# IP2363_DEMO_V1_10.net
KiCad netlist of a schematic drawn in Altium Designer
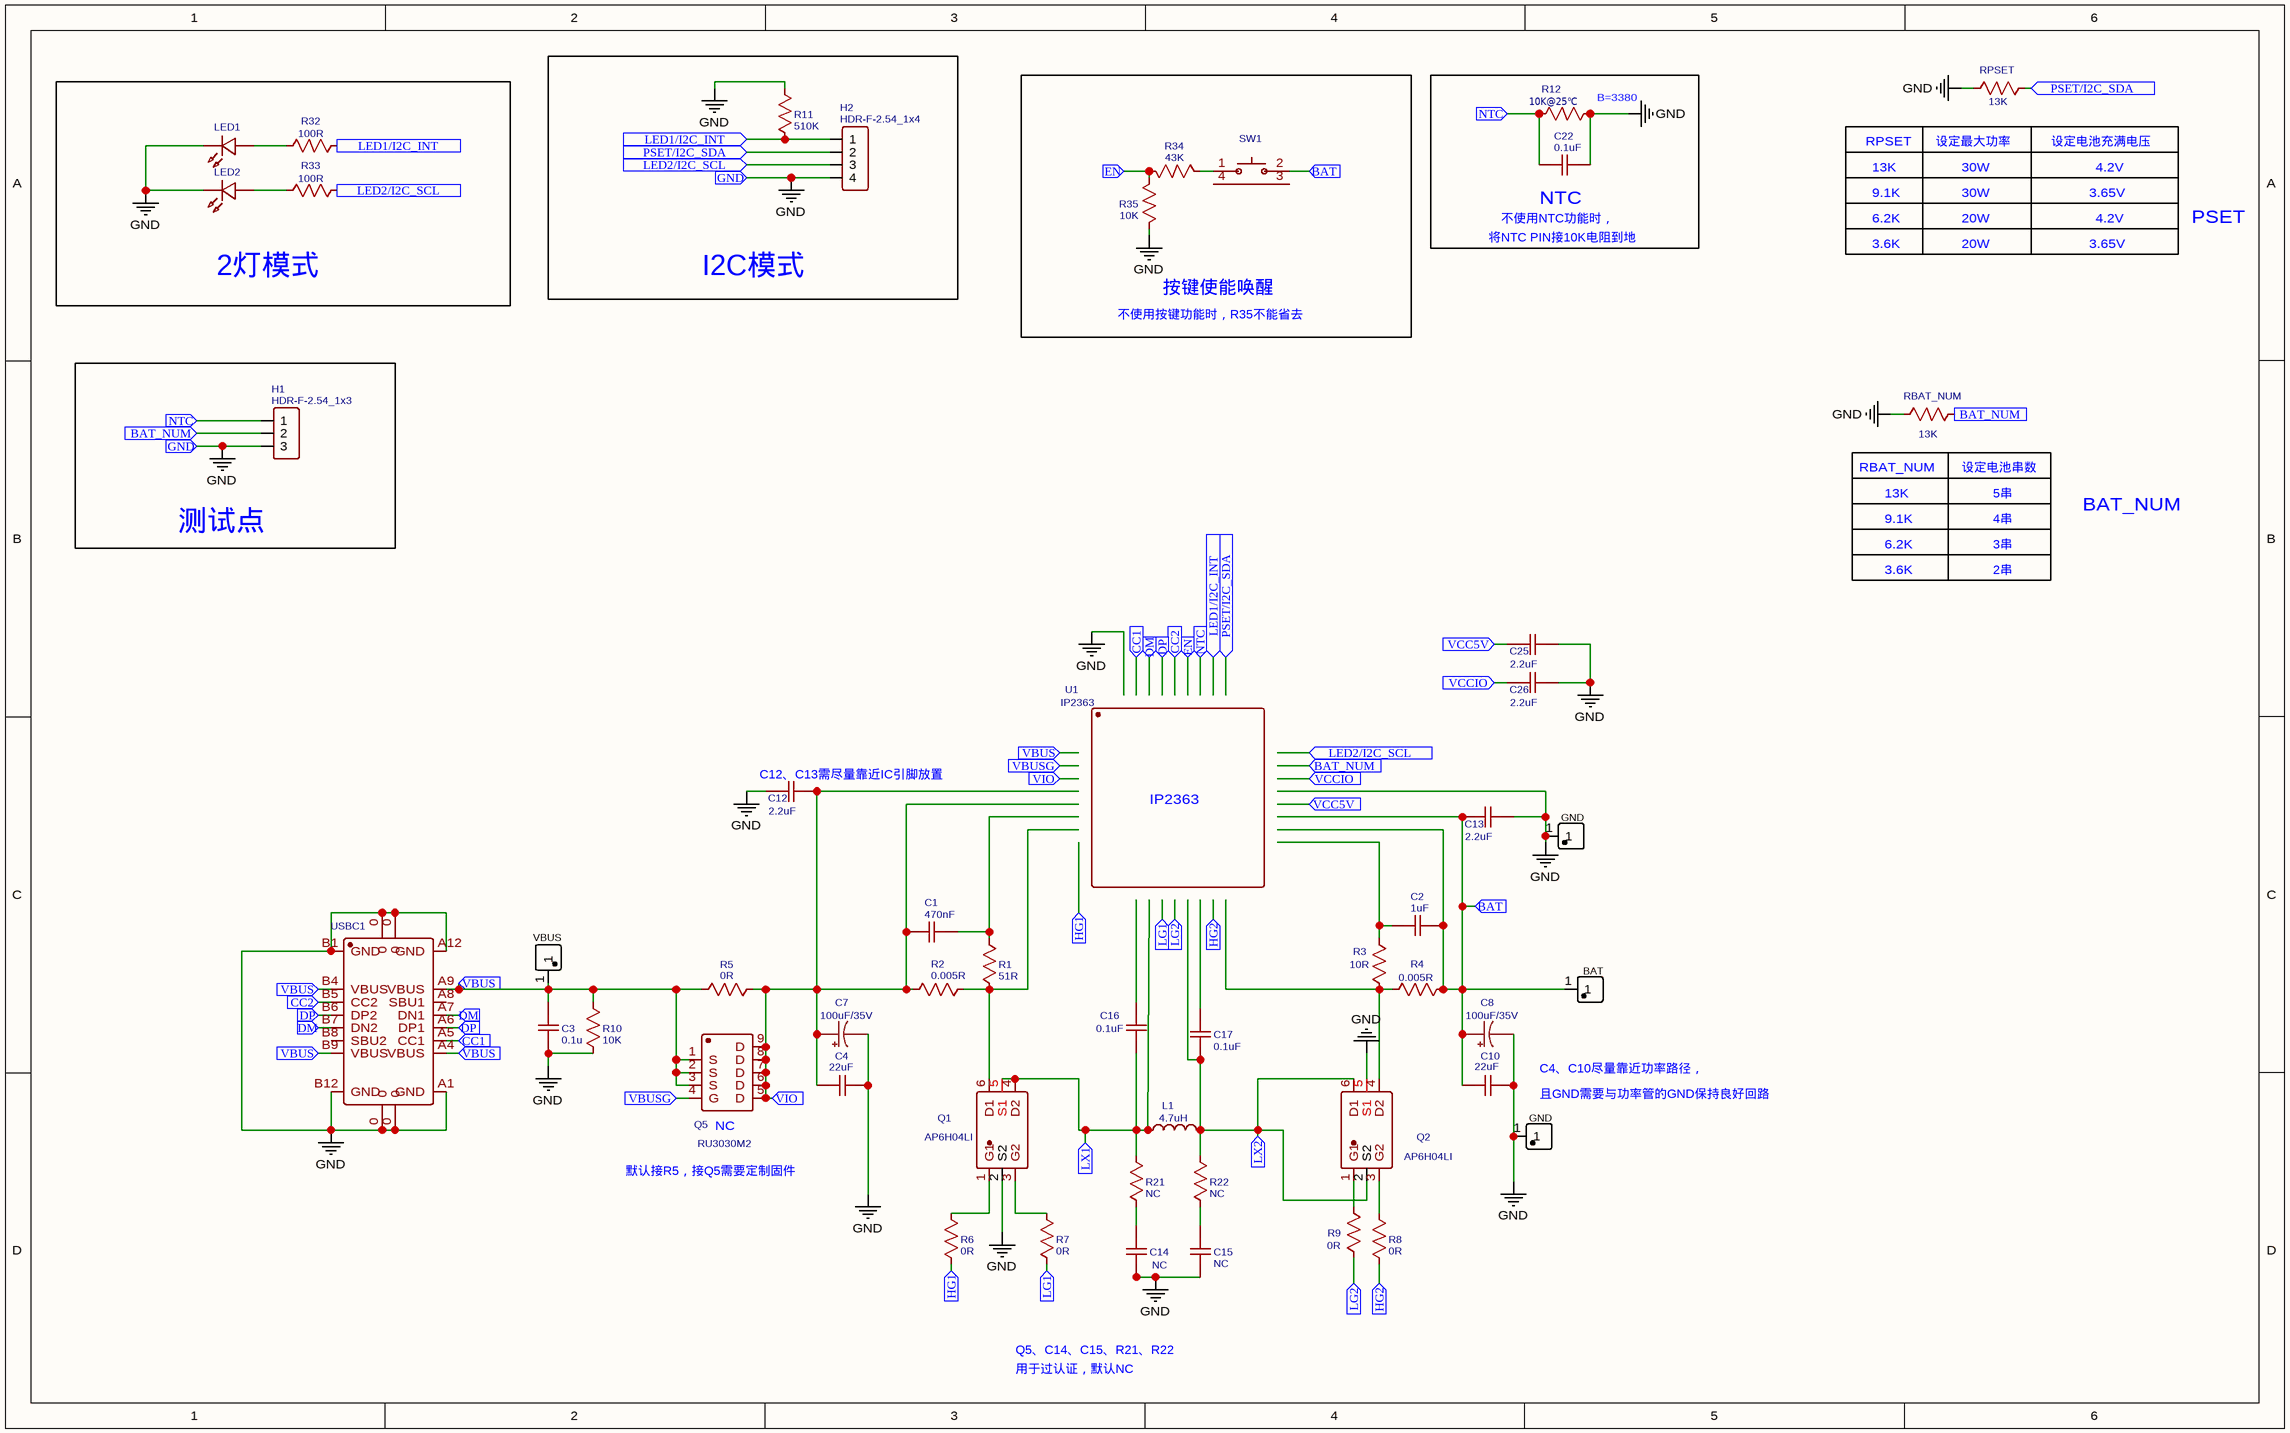
[diagram p0: IP2363_DEMO_V1.10.schdoc]

(export (version "E")
  (design (tool "Eeschema 10.0.6"))
  (components
    (comp (ref "C1")
      (value "470nF")
      (fields (field (name "CONTRIBUTOR") "LCEDA_Lib"))
      (libsource (lib "altium-import") (part "root_0_470nF_"))
    )
    (comp (ref "C2")
      (value "1uF")
      (fields (field (name "CONTRIBUTOR") "LCEDA_Lib"))
      (libsource (lib "altium-import") (part "root_0_1uF_"))
    )
    (comp (ref "C3")
      (value "0.1u")
      (fields (field (name "CONTRIBUTOR") "LCEDA_Lib"))
      (libsource (lib "altium-import") (part "root_1_0.1u_"))
    )
    (comp (ref "C4")
      (value "22uF")
      (fields (field (name "CONTRIBUTOR") "LCEDA_Lib"))
      (libsource (lib "altium-import") (part "root_0_22uF_"))
    )
    (comp (ref "C7")
      (value "100uF/35V")
      (fields
        (field (name "BOM_SUPPLIER PART") "C365767")
        (field (name "BOM_MANUFACTURER PART") "RC050M4R7LO5*11TH-2A1E")
        (field (name "CONTRIBUTOR") "s-dawn")
      )
      (libsource (lib "altium-import") (part "root_1_100uF/35V_"))
    )
    (comp (ref "C8")
      (value "100uF/35V")
      (fields
        (field (name "BOM_SUPPLIER PART") "C365767")
        (field (name "BOM_MANUFACTURER PART") "RC050M4R7LO5*11TH-2A1E")
        (field (name "CONTRIBUTOR") "s-dawn")
      )
      (libsource (lib "altium-import") (part "root_1_100uF/35V_"))
    )
    (comp (ref "C10")
      (value "22uF")
      (fields (field (name "CONTRIBUTOR") "LCEDA_Lib"))
      (libsource (lib "altium-import") (part "root_0_22uF_"))
    )
    (comp (ref "C12")
      (value "2.2uF")
      (fields (field (name "CONTRIBUTOR") "LCEDA_Lib"))
      (libsource (lib "altium-import") (part "root_0_2.2uF_"))
    )
    (comp (ref "C13")
      (value "2.2uF")
      (fields (field (name "CONTRIBUTOR") "LCEDA_Lib"))
      (libsource (lib "altium-import") (part "root_0_2.2uF_"))
    )
    (comp (ref "C14")
      (value "NC")
      (fields (field (name "CONTRIBUTOR") "LCEDA_Lib"))
      (libsource (lib "altium-import") (part "root_3_NC_"))
    )
    (comp (ref "C15")
      (value "NC")
      (fields (field (name "CONTRIBUTOR") "LCEDA_Lib"))
      (libsource (lib "altium-import") (part "root_3_NC_"))
    )
    (comp (ref "C16")
      (value "0.1uF")
      (fields (field (name "CONTRIBUTOR") "LCEDA_Lib"))
      (libsource (lib "altium-import") (part "root_3_0.1uF_"))
    )
    (comp (ref "C17")
      (value "0.1uF")
      (fields (field (name "CONTRIBUTOR") "LCEDA_Lib"))
      (libsource (lib "altium-import") (part "root_3_0.1uF_"))
    )
    (comp (ref "C22")
      (value "0.1uF")
      (fields (field (name "CONTRIBUTOR") "LCEDA_Lib"))
      (libsource (lib "altium-import") (part "root_0_0.1uF_"))
    )
    (comp (ref "C25")
      (value "2.2uF")
      (fields (field (name "CONTRIBUTOR") "LCEDA_Lib"))
      (libsource (lib "altium-import") (part "root_0_2.2uF_"))
    )
    (comp (ref "C26")
      (value "2.2uF")
      (fields (field (name "CONTRIBUTOR") "LCEDA_Lib"))
      (libsource (lib "altium-import") (part "root_0_2.2uF_"))
    )
    (comp (ref "H1")
      (value "HDR-F-2.54_1x3")
      (fields (field (name "BOM_SUPPLIER PART") "C146690") (field (name "CONTRIBUTOR") "LCEDA_Lib"))
      (libsource (lib "altium-import") (part "root_0_HDR-F-2.54_1x3_"))
    )
    (comp (ref "H2")
      (value "HDR-F-2.54_1x4")
      (fields (field (name "BOM_SUPPLIER PART") "C225501") (field (name "CONTRIBUTOR") "LCEDA_Lib"))
      (libsource (lib "altium-import") (part "root_0_HDR-F-2.54_1x4_"))
    )
    (comp (ref "L1")
      (value "4.7uH")
      (fields
        (field (name "BOM_SUPPLIER PART") "C526015")
        (field (name "BOM_MANUFACTURER PART") "FXL1350-4R7-M")
        (field (name "CONTRIBUTOR") "LCSC")
      )
      (libsource (lib "altium-import") (part "root_0_4.7uH_"))
    )
    (comp (ref "LED1")
      (value "LED-0603_B")
      (fields
        (field (name "BOM_MANUFACTURER PART") "19-217/BHC-ZL1M2RY/3T")
        (field (name "BOM_SUPPLIER PART") "C72041")
        (field (name "CONTRIBUTOR") "LCEDA_01")
      )
      (libsource (lib "altium-import") (part "root_2_LED-0603_B_"))
    )
    (comp (ref "LED2")
      (value "LED-0603_B")
      (fields
        (field (name "BOM_MANUFACTURER PART") "19-217/BHC-ZL1M2RY/3T")
        (field (name "BOM_SUPPLIER PART") "C72041")
        (field (name "CONTRIBUTOR") "LCEDA_01")
      )
      (libsource (lib "altium-import") (part "root_2_LED-0603_B_"))
    )
    (comp (ref "Q1")
      (value "AP6H04LI")
      (fields (field (name "CONTRIBUTOR") "it809"))
      (libsource (lib "altium-import") (part "root_1_AP6H04LI_"))
    )
    (comp (ref "Q2")
      (value "AP6H04LI")
      (fields (field (name "CONTRIBUTOR") "it809"))
      (libsource (lib "altium-import") (part "root_1_AP6H04LI_"))
    )
    (comp (ref "Q5")
      (value "RU3030M2")
      (fields (field (name "BOM_SUPPLIER PART") "C180957") (field (name "CONTRIBUTOR") "LCSC"))
      (libsource (lib "altium-import") (part "root_0_RU3030M2_"))
    )
    (comp (ref "R1")
      (value "51R")
      (fields (field (name "CONTRIBUTOR") "LCEDA_Lib"))
      (libsource (lib "altium-import") (part "root_1_51R_"))
    )
    (comp (ref "R2")
      (value "0.005R")
      (fields (field (name "CONTRIBUTOR") "LCEDA_Lib"))
      (libsource (lib "altium-import") (part "root_0_0.005R_"))
    )
    (comp (ref "R3")
      (value "10R")
      (fields (field (name "CONTRIBUTOR") "LCEDA_Lib"))
      (libsource (lib "altium-import") (part "root_1_10R_"))
    )
    (comp (ref "R4")
      (value "0.005R")
      (fields (field (name "CONTRIBUTOR") "LCEDA_Lib"))
      (libsource (lib "altium-import") (part "root_0_0.005R_"))
    )
    (comp (ref "R5")
      (value "0R")
      (fields (field (name "CONTRIBUTOR") "LCEDA_Lib"))
      (libsource (lib "altium-import") (part "root_0_0R_"))
    )
    (comp (ref "R6")
      (value "0R")
      (fields (field (name "CONTRIBUTOR") "LCEDA_Lib"))
      (libsource (lib "altium-import") (part "root_3_0R_"))
    )
    (comp (ref "R7")
      (value "0R")
      (fields (field (name "CONTRIBUTOR") "LCEDA_Lib"))
      (libsource (lib "altium-import") (part "root_3_0R_"))
    )
    (comp (ref "R8")
      (value "0R")
      (fields (field (name "CONTRIBUTOR") "LCEDA_Lib"))
      (libsource (lib "altium-import") (part "root_3_0R_"))
    )
    (comp (ref "R9")
      (value "0R")
      (fields (field (name "CONTRIBUTOR") "LCEDA_Lib"))
      (libsource (lib "altium-import") (part "root_3_0R_"))
    )
    (comp (ref "R10")
      (value "10K")
      (fields (field (name "CONTRIBUTOR") "LCEDA_Lib"))
      (libsource (lib "altium-import") (part "root_3_10K_"))
    )
    (comp (ref "R11")
      (value "510K")
      (fields (field (name "CONTRIBUTOR") "LCEDA_Lib"))
      (libsource (lib "altium-import") (part "root_3_510K_"))
    )
    (comp (ref "R12")
      (value "10K@25℃")
      (fields (field (name "CONTRIBUTOR") "LCEDA_Lib"))
      (libsource (lib "altium-import") (part "root_2_10K@25℃_"))
    )
    (comp (ref "R21")
      (value "NC")
      (fields (field (name "CONTRIBUTOR") "LCEDA_Lib"))
      (libsource (lib "altium-import") (part "root_1_NC_"))
    )
    (comp (ref "R22")
      (value "NC")
      (fields (field (name "CONTRIBUTOR") "LCEDA_Lib"))
      (libsource (lib "altium-import") (part "root_1_NC_"))
    )
    (comp (ref "R32")
      (value "100R")
      (fields (field (name "CONTRIBUTOR") "LCEDA_Lib"))
      (libsource (lib "altium-import") (part "root_2_100R_"))
    )
    (comp (ref "R33")
      (value "100R")
      (fields (field (name "CONTRIBUTOR") "LCEDA_Lib"))
      (libsource (lib "altium-import") (part "root_2_100R_"))
    )
    (comp (ref "R34")
      (value "43K")
      (fields (field (name "CONTRIBUTOR") "LCEDA_Lib"))
      (libsource (lib "altium-import") (part "root_2_43K_"))
    )
    (comp (ref "R35")
      (value "10K")
      (fields (field (name "CONTRIBUTOR") "LCEDA_Lib"))
      (libsource (lib "") (part "root_3_10K__1"))
    )
    (comp (ref "RBAT_NUM")
      (value "13K")
      (fields (field (name "CONTRIBUTOR") "LCEDA_Lib"))
      (libsource (lib "altium-import") (part "root_0_13K_"))
    )
    (comp (ref "RPSET")
      (value "13K")
      (fields (field (name "CONTRIBUTOR") "LCEDA_Lib"))
      (libsource (lib "altium-import") (part "root_0_13K_"))
    )
    (comp (ref "SW1")
      (value "1TS002G-1900-3500-CT")
      (fields (field (name "BOM_SUPPLIER PART") "C319376") (field (name "CONTRIBUTOR") "LCSC"))
      (libsource (lib "altium-import") (part "root_0_1TS002G-1900-3500-CT_"))
    )
    (comp (ref "U1")
      (value "IP2363")
      (fields (field (name "CONTRIBUTOR") "cong24"))
      (libsource (lib "altium-import") (part "root_0_IP2363_"))
    )
    (comp (ref "U2")
      (value "VBUS")
      (fields
        (field (name "BOM_SUPPLIER PART") "C9900007423")
        (field (name "BOM_MANUFACTURER PART") "TP-红色测试点")
        (field (name "CONTRIBUTOR") "lcsc")
      )
      (libsource (lib "altium-import") (part "root_3_VBUS_"))
    )
    (comp (ref "U3")
      (value "GND")
      (fields
        (field (name "BOM_SUPPLIER PART") "C9900007423")
        (field (name "BOM_MANUFACTURER PART") "TP-红色测试点")
        (field (name "CONTRIBUTOR") "lcsc")
      )
      (libsource (lib "altium-import") (part "root_2_GND_"))
    )
    (comp (ref "U4")
      (value "BAT")
      (fields
        (field (name "BOM_SUPPLIER PART") "C9900007423")
        (field (name "BOM_MANUFACTURER PART") "TP-红色测试点")
        (field (name "CONTRIBUTOR") "lcsc")
      )
      (libsource (lib "altium-import") (part "root_2_BAT_"))
    )
    (comp (ref "U5")
      (value "GND")
      (fields
        (field (name "BOM_SUPPLIER PART") "C9900007423")
        (field (name "BOM_MANUFACTURER PART") "TP-红色测试点")
        (field (name "CONTRIBUTOR") "lcsc")
      )
      (libsource (lib "altium-import") (part "root_2_GND_"))
    )
    (comp (ref "USBC1")
      (value "TYPE-C-31-M-12")
      (fields (field (name "BOM_SUPPLIER PART") "C165948") (field (name "CONTRIBUTOR") "LCSC"))
      (libsource (lib "altium-import") (part "root_0_TYPE-C-31-M-12_"))
    )
  )
  (nets
    (net (code "1") (name "/BAT") (class "Default")
      (node (ref "C10") (pin "1") (pinfunction "1_1") (pintype "passive"))
      (node (ref "C13") (pin "1") (pinfunction "1_1") (pintype "passive"))
      (node (ref "C2") (pin "2") (pinfunction "2_2") (pintype "passive"))
      (node (ref "C8") (pin "1") (pinfunction "1_1") (pintype "passive"))
      (node (ref "R4") (pin "2") (pinfunction "2_2") (pintype "passive"))
      (node (ref "SW1") (pin "2") (pinfunction "2_2") (pintype "passive"))
      (node (ref "U4") (pin "1") (pinfunction "1_1") (pintype "passive"))
    )
    (net (code "2") (name "/BAT_NUM") (class "Default")
      (node (ref "H1") (pin "2") (pinfunction "2_2") (pintype "passive"))
      (node (ref "RBAT_NUM") (pin "2") (pinfunction "2_2") (pintype "passive"))
    )
    (net (code "3") (name "/CC1") (class "Default")
      (node (ref "USBC1") (pin "A5") (pinfunction "CC1_A5") (pintype "passive"))
    )
    (net (code "4") (name "/CC2") (class "Default")
      (node (ref "USBC1") (pin "B5") (pinfunction "CC2_B5") (pintype "passive"))
    )
    (net (code "5") (name "/DM") (class "Default")
      (node (ref "USBC1") (pin "A7") (pinfunction "DN1_A7") (pintype "passive"))
      (node (ref "USBC1") (pin "B7") (pinfunction "DN2_B7") (pintype "passive"))
    )
    (net (code "6") (name "/DP") (class "Default")
      (node (ref "USBC1") (pin "A6") (pinfunction "DP1_A6") (pintype "passive"))
      (node (ref "USBC1") (pin "B6") (pinfunction "DP2_B6") (pintype "passive"))
    )
    (net (code "7") (name "/EN") (class "Default")
      (node (ref "R34") (pin "1") (pinfunction "1_1") (pintype "passive"))
      (node (ref "R35") (pin "1") (pinfunction "1_1") (pintype "passive"))
    )
    (net (code "8") (name "/HG1") (class "Default")
      (node (ref "R6") (pin "2") (pinfunction "2_2") (pintype "passive"))
    )
    (net (code "9") (name "/HG2") (class "Default")
      (node (ref "R8") (pin "2") (pinfunction "2_2") (pintype "passive"))
    )
    (net (code "10") (name "/LED1{slash}I2C_INT") (class "Default")
      (node (ref "H2") (pin "1") (pinfunction "1_1") (pintype "passive"))
      (node (ref "R11") (pin "2") (pinfunction "2_2") (pintype "passive"))
      (node (ref "R32") (pin "1") (pinfunction "1_1") (pintype "passive"))
    )
    (net (code "11") (name "/LED2{slash}I2C_SCL") (class "Default")
      (node (ref "H2") (pin "3") (pinfunction "3_3") (pintype "passive"))
      (node (ref "R33") (pin "1") (pinfunction "1_1") (pintype "passive"))
    )
    (net (code "12") (name "/LG1") (class "Default")
      (node (ref "R7") (pin "2") (pinfunction "2_2") (pintype "passive"))
    )
    (net (code "13") (name "/LG2") (class "Default")
      (node (ref "R9") (pin "2") (pinfunction "2_2") (pintype "passive"))
    )
    (net (code "14") (name "/LX1") (class "Default")
      (node (ref "C16") (pin "2") (pinfunction "2_2") (pintype "passive"))
      (node (ref "L1") (pin "1") (pinfunction "1_1") (pintype "passive"))
      (node (ref "Q1") (pin "4") (pinfunction "D2_4") (pintype "passive"))
      (node (ref "Q1") (pin "5") (pinfunction "S1_5") (pintype "passive"))
      (node (ref "R21") (pin "2") (pinfunction "2_2") (pintype "passive"))
    )
    (net (code "15") (name "/LX2") (class "Default")
      (node (ref "C17") (pin "2") (pinfunction "2_2") (pintype "passive"))
      (node (ref "L1") (pin "2") (pinfunction "2_2") (pintype "passive"))
      (node (ref "Q2") (pin "2") (pinfunction "S2_2") (pintype "passive"))
      (node (ref "Q2") (pin "6") (pinfunction "D1_6") (pintype "passive"))
      (node (ref "R22") (pin "2") (pinfunction "2_2") (pintype "passive"))
    )
    (net (code "16") (name "/NTC") (class "Default")
      (node (ref "C22") (pin "1") (pinfunction "1_1") (pintype "passive"))
      (node (ref "H1") (pin "1") (pinfunction "1_1") (pintype "passive"))
      (node (ref "R12") (pin "2") (pinfunction "2_2") (pintype "passive"))
    )
    (net (code "17") (name "/PSET{slash}I2C_SDA") (class "Default")
      (node (ref "H2") (pin "2") (pinfunction "2_2") (pintype "passive"))
      (node (ref "RPSET") (pin "2") (pinfunction "2_2") (pintype "passive"))
    )
    (net (code "18") (name "/VBUS") (class "Default")
      (node (ref "C3") (pin "2") (pinfunction "2_2") (pintype "passive"))
      (node (ref "Q5") (pin "1") (pinfunction "S_1") (pintype "passive"))
      (node (ref "Q5") (pin "2") (pinfunction "S_2") (pintype "passive"))
      (node (ref "Q5") (pin "3") (pinfunction "S_3") (pintype "passive"))
      (node (ref "R10") (pin "1") (pinfunction "1_1") (pintype "passive"))
      (node (ref "R5") (pin "1") (pinfunction "1_1") (pintype "passive"))
      (node (ref "U2") (pin "1") (pinfunction "1_1") (pintype "passive"))
      (node (ref "USBC1") (pin "A4") (pinfunction "VBUS_A4") (pintype "passive"))
      (node (ref "USBC1") (pin "A9") (pinfunction "VBUS_A9") (pintype "passive"))
      (node (ref "USBC1") (pin "B4") (pinfunction "VBUS_B4") (pintype "passive"))
      (node (ref "USBC1") (pin "B9") (pinfunction "VBUS_B9") (pintype "passive"))
    )
    (net (code "19") (name "/VBUSG") (class "Default")
      (node (ref "Q5") (pin "4") (pinfunction "G_4") (pintype "passive"))
    )
    (net (code "20") (name "/VCC5V") (class "Default")
      (node (ref "C25") (pin "1") (pinfunction "1_1") (pintype "passive"))
    )
    (net (code "21") (name "/VCCIO") (class "Default")
      (node (ref "C26") (pin "1") (pinfunction "1_1") (pintype "passive"))
    )
    (net (code "22") (name "/VIO") (class "Default")
      (node (ref "C1") (pin "1") (pinfunction "1_1") (pintype "passive"))
      (node (ref "C12") (pin "2") (pinfunction "2_2") (pintype "passive"))
      (node (ref "C4") (pin "1") (pinfunction "1_1") (pintype "passive"))
      (node (ref "C7") (pin "1") (pinfunction "1_1") (pintype "passive"))
      (node (ref "Q5") (pin "5") (pinfunction "D_5") (pintype "passive"))
      (node (ref "Q5") (pin "6") (pinfunction "D_6") (pintype "passive"))
      (node (ref "Q5") (pin "7") (pinfunction "D_7") (pintype "passive"))
      (node (ref "Q5") (pin "8") (pinfunction "D_8") (pintype "passive"))
      (node (ref "Q5") (pin "9") (pinfunction "D_9") (pintype "passive"))
      (node (ref "R2") (pin "1") (pinfunction "1_1") (pintype "passive"))
      (node (ref "R5") (pin "2") (pinfunction "2_2") (pintype "passive"))
    )
    (net (code "23") (name "GND") (class "Default")
      (node (ref "C10") (pin "2") (pinfunction "2_2") (pintype "passive"))
      (node (ref "C12") (pin "1") (pinfunction "1_1") (pintype "passive"))
      (node (ref "C13") (pin "2") (pinfunction "2_2") (pintype "passive"))
      (node (ref "C14") (pin "2") (pinfunction "2_2") (pintype "passive"))
      (node (ref "C15") (pin "2") (pinfunction "2_2") (pintype "passive"))
      (node (ref "C22") (pin "2") (pinfunction "2_2") (pintype "passive"))
      (node (ref "C25") (pin "2") (pinfunction "2_2") (pintype "passive"))
      (node (ref "C26") (pin "2") (pinfunction "2_2") (pintype "passive"))
      (node (ref "C3") (pin "1") (pinfunction "1_1") (pintype "passive"))
      (node (ref "C4") (pin "2") (pinfunction "2_2") (pintype "passive"))
      (node (ref "C7") (pin "2") (pinfunction "2_2") (pintype "passive"))
      (node (ref "C8") (pin "2") (pinfunction "2_2") (pintype "passive"))
      (node (ref "H1") (pin "3") (pinfunction "3_3") (pintype "passive"))
      (node (ref "H2") (pin "4") (pinfunction "4_4") (pintype "passive"))
      (node (ref "LED1") (pin "2") (pinfunction "2_2") (pintype "passive"))
      (node (ref "LED2") (pin "2") (pinfunction "2_2") (pintype "passive"))
      (node (ref "Q1") (pin "2") (pinfunction "S2_2") (pintype "passive"))
      (node (ref "Q2") (pin "5") (pinfunction "S1_5") (pintype "passive"))
      (node (ref "R10") (pin "2") (pinfunction "2_2") (pintype "passive"))
      (node (ref "R11") (pin "1") (pinfunction "1_1") (pintype "passive"))
      (node (ref "R12") (pin "1") (pinfunction "1_1") (pintype "passive"))
      (node (ref "R35") (pin "2") (pinfunction "2_2") (pintype "passive"))
      (node (ref "RBAT_NUM") (pin "1") (pinfunction "1_1") (pintype "passive"))
      (node (ref "RPSET") (pin "1") (pinfunction "1_1") (pintype "passive"))
      (node (ref "U3") (pin "1") (pinfunction "1_1") (pintype "passive"))
      (node (ref "U5") (pin "1") (pinfunction "1_1") (pintype "passive"))
      (node (ref "USBC1") (pin "0") (pinfunction "0_0") (pintype "passive"))
      (node (ref "USBC1") (pin "A1") (pinfunction "GND_A1") (pintype "passive"))
      (node (ref "USBC1") (pin "A12") (pinfunction "GND_A12") (pintype "passive"))
      (node (ref "USBC1") (pin "B1") (pinfunction "GND_B1") (pintype "passive"))
      (node (ref "USBC1") (pin "B12") (pinfunction "GND_B12") (pintype "passive"))
    )
    (net (code "24") (name "Net-(C1-Pad2)") (class "Default")
      (node (ref "C1") (pin "2") (pinfunction "2_2") (pintype "passive"))
      (node (ref "R1") (pin "2") (pinfunction "2_2") (pintype "passive"))
    )
    (net (code "25") (name "Net-(C2-Pad1)") (class "Default")
      (node (ref "C2") (pin "1") (pinfunction "1_1") (pintype "passive"))
      (node (ref "R3") (pin "2") (pinfunction "2_2") (pintype "passive"))
    )
    (net (code "26") (name "Net-(C14-Pad1)") (class "Default")
      (node (ref "C14") (pin "1") (pinfunction "1_1") (pintype "passive"))
      (node (ref "R21") (pin "1") (pinfunction "1_1") (pintype "passive"))
    )
    (net (code "27") (name "Net-(C15-Pad1)") (class "Default")
      (node (ref "C15") (pin "1") (pinfunction "1_1") (pintype "passive"))
      (node (ref "R22") (pin "1") (pinfunction "1_1") (pintype "passive"))
    )
    (net (code "28") (name "Net-(LED1-Pad1)") (class "Default")
      (node (ref "LED1") (pin "1") (pinfunction "1_1") (pintype "passive"))
      (node (ref "R32") (pin "2") (pinfunction "2_2") (pintype "passive"))
    )
    (net (code "29") (name "Net-(LED2-Pad1)") (class "Default")
      (node (ref "LED2") (pin "1") (pinfunction "1_1") (pintype "passive"))
      (node (ref "R33") (pin "2") (pinfunction "2_2") (pintype "passive"))
    )
    (net (code "30") (name "Net-(Q1-D1)") (class "Default")
      (node (ref "Q1") (pin "6") (pinfunction "D1_6") (pintype "passive"))
      (node (ref "R1") (pin "1") (pinfunction "1_1") (pintype "passive"))
      (node (ref "R2") (pin "2") (pinfunction "2_2") (pintype "passive"))
    )
    (net (code "31") (name "Net-(Q1-G1)") (class "Default")
      (node (ref "Q1") (pin "1") (pinfunction "G1_1") (pintype "passive"))
      (node (ref "R6") (pin "1") (pinfunction "1_1") (pintype "passive"))
    )
    (net (code "32") (name "Net-(Q1-G2)") (class "Default")
      (node (ref "Q1") (pin "3") (pinfunction "G2_3") (pintype "passive"))
      (node (ref "R7") (pin "1") (pinfunction "1_1") (pintype "passive"))
    )
    (net (code "33") (name "Net-(Q2-D2)") (class "Default")
      (node (ref "Q2") (pin "4") (pinfunction "D2_4") (pintype "passive"))
      (node (ref "R3") (pin "1") (pinfunction "1_1") (pintype "passive"))
      (node (ref "R4") (pin "1") (pinfunction "1_1") (pintype "passive"))
    )
    (net (code "34") (name "Net-(Q2-G1)") (class "Default")
      (node (ref "Q2") (pin "1") (pinfunction "G1_1") (pintype "passive"))
      (node (ref "R9") (pin "1") (pinfunction "1_1") (pintype "passive"))
    )
    (net (code "35") (name "Net-(Q2-G2)") (class "Default")
      (node (ref "Q2") (pin "3") (pinfunction "G2_3") (pintype "passive"))
      (node (ref "R8") (pin "1") (pinfunction "1_1") (pintype "passive"))
    )
    (net (code "36") (name "Net-(R34-Pad2)") (class "Default")
      (node (ref "R34") (pin "2") (pinfunction "2_2") (pintype "passive"))
      (node (ref "SW1") (pin "1") (pinfunction "1_1") (pintype "passive"))
    )
    (net (code "37") (name "unconnected-(C16-Pad1)") (class "Default")
      (node (ref "C16") (pin "1") (pinfunction "1_1") (pintype "passive"))
    )
    (net (code "38") (name "unconnected-(C17-Pad1)") (class "Default")
      (node (ref "C17") (pin "1") (pinfunction "1_1") (pintype "passive"))
    )
    (net (code "39") (name "unconnected-(SW1-Pad3)") (class "Default")
      (node (ref "SW1") (pin "3") (pinfunction "3_3") (pintype "passive"))
    )
    (net (code "40") (name "unconnected-(SW1-Pad4)") (class "Default")
      (node (ref "SW1") (pin "4") (pinfunction "4_4") (pintype "passive"))
    )
    (net (code "41") (name "unconnected-(USBC1-SBU1-PadA8)") (class "Default")
      (node (ref "USBC1") (pin "A8") (pinfunction "SBU1_A8") (pintype "passive"))
    )
    (net (code "42") (name "unconnected-(USBC1-SBU2-PadB8)") (class "Default")
      (node (ref "USBC1") (pin "B8") (pinfunction "SBU2_B8") (pintype "passive"))
    )
  )
)
